# memory.net
KiCad netlist of a schematic drawn in Altium Designer
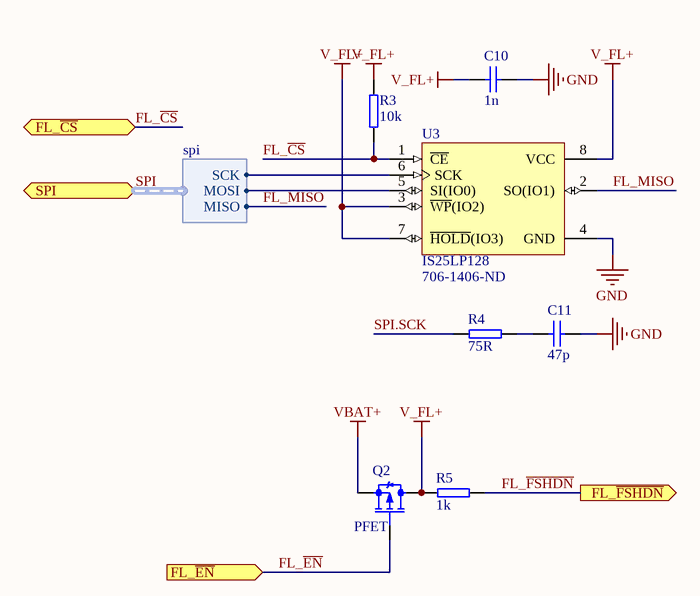
[diagram p0: memory.SchDoc]

(export (version "E")
  (design (tool "Eeschema 10.0.6"))
  (components
    (comp (ref "C10")
      (value "1n")
      (footprint "CAPC1608X95N")
      (description "Capacitor")
      (fields (field (name "VOLTAGE") "50V"))
      (libsource (lib "rlc") (part "C"))
    )
    (comp (ref "C11")
      (value "47p")
      (footprint "CAPC1608X95N")
      (description "Capacitor")
      (fields (field (name "VOLTAGE") "50V"))
      (libsource (lib "rlc") (part "C"))
    )
    (comp (ref "Q2")
      (value "PFET")
      (footprint "SOT95P237X112-3N")
      (description "P-Channel MOSFET, 20V 2.6A")
      (libsource (lib "transistor") (part "IRLML2246TRPBF"))
    )
    (comp (ref "R3")
      (value "10k")
      (footprint "RESC1608X55N")
      (description "Resistor")
      (libsource (lib "rlc") (part "R"))
    )
    (comp (ref "R4")
      (value "75R")
      (footprint "RESC1608X55N")
      (description "Resistor")
      (libsource (lib "rlc") (part "R"))
    )
    (comp (ref "R5")
      (value "1k")
      (footprint "RESC1608X55N")
      (description "Resistor")
      (libsource (lib "rlc") (part "R"))
    )
    (comp (ref "U3")
      (value "IS25LP128")
      (footprint "QFN127P500X600X80-8M_MIN_EP")
      (description "3V SERIAL FLASH MEMORY WITH 133MHZ MULTI  I/O   SPI & QUAD I/O QPI DTR INTERFACE")
      (fields (field (name "SUPPLIER PART NUMBER 1") "706-1406-ND"))
      (libsource (lib "memory") (part "IS25LP128"))
    )
  )
  (nets
    (net (code "2") (name "/FL_MISO") (class "Default")
      (node (ref "U3") (pin "2") (pinfunction "SO(IO1)_2") (pintype "bidirectional"))
    )
    (net (code "3") (name "/FL_~{CS}") (class "Default")
      (node (ref "R3") (pin "1") (pinfunction "1_1") (pintype "passive"))
      (node (ref "U3") (pin "1") (pinfunction "~{CE}_1") (pintype "input"))
    )
    (net (code "4") (name "/FL_~{EN}") (class "Default")
      (node (ref "Q2") (pin "1") (pinfunction "G_1") (pintype "passive"))
    )
    (net (code "5") (name "/FL_~{FSHDN}") (class "Default")
      (node (ref "R5") (pin "2") (pinfunction "2_2") (pintype "passive"))
    )
    (net (code "6") (name "/MOSI") (class "Default")
      (node (ref "U3") (pin "5") (pinfunction "SI(IO0)_5") (pintype "bidirectional"))
    )
    (net (code "7") (name "/SCK") (class "Default")
      (node (ref "U3") (pin "6") (pinfunction "SCK_6") (pintype "input"))
    )
    (net (code "8") (name "/SPI.SCK") (class "Default")
      (node (ref "R4") (pin "1") (pinfunction "1_1") (pintype "passive"))
    )
    (net (code "10") (name "GND") (class "Default")
      (node (ref "C10") (pin "1") (pinfunction "1_1") (pintype "passive"))
      (node (ref "C11") (pin "2") (pinfunction "2_2") (pintype "passive"))
      (node (ref "U3") (pin "4") (pinfunction "GND_4") (pintype "power_in"))
    )
    (net (code "11") (name "Net-(C11-Pad1)") (class "Default")
      (node (ref "C11") (pin "1") (pinfunction "1_1") (pintype "passive"))
      (node (ref "R4") (pin "2") (pinfunction "2_2") (pintype "passive"))
    )
    (net (code "12") (name "VBAT+") (class "Default")
      (node (ref "Q2") (pin "2") (pinfunction "S_2") (pintype "passive"))
    )
    (net (code "13") (name "V_FL+") (class "Default")
      (node (ref "C10") (pin "2") (pinfunction "2_2") (pintype "passive"))
      (node (ref "Q2") (pin "3") (pinfunction "D_3") (pintype "passive"))
      (node (ref "R3") (pin "2") (pinfunction "2_2") (pintype "passive"))
      (node (ref "R5") (pin "1") (pinfunction "1_1") (pintype "passive"))
      (node (ref "U3") (pin "3") (pinfunction "~{WP}(IO2)_3") (pintype "bidirectional"))
      (node (ref "U3") (pin "7") (pinfunction "~{HOLD}(IO3)_7") (pintype "bidirectional"))
      (node (ref "U3") (pin "8") (pinfunction "VCC_8") (pintype "power_in"))
    )
  )
)
